# ASL2111.net
KiCad netlist of a schematic drawn in EAGLE
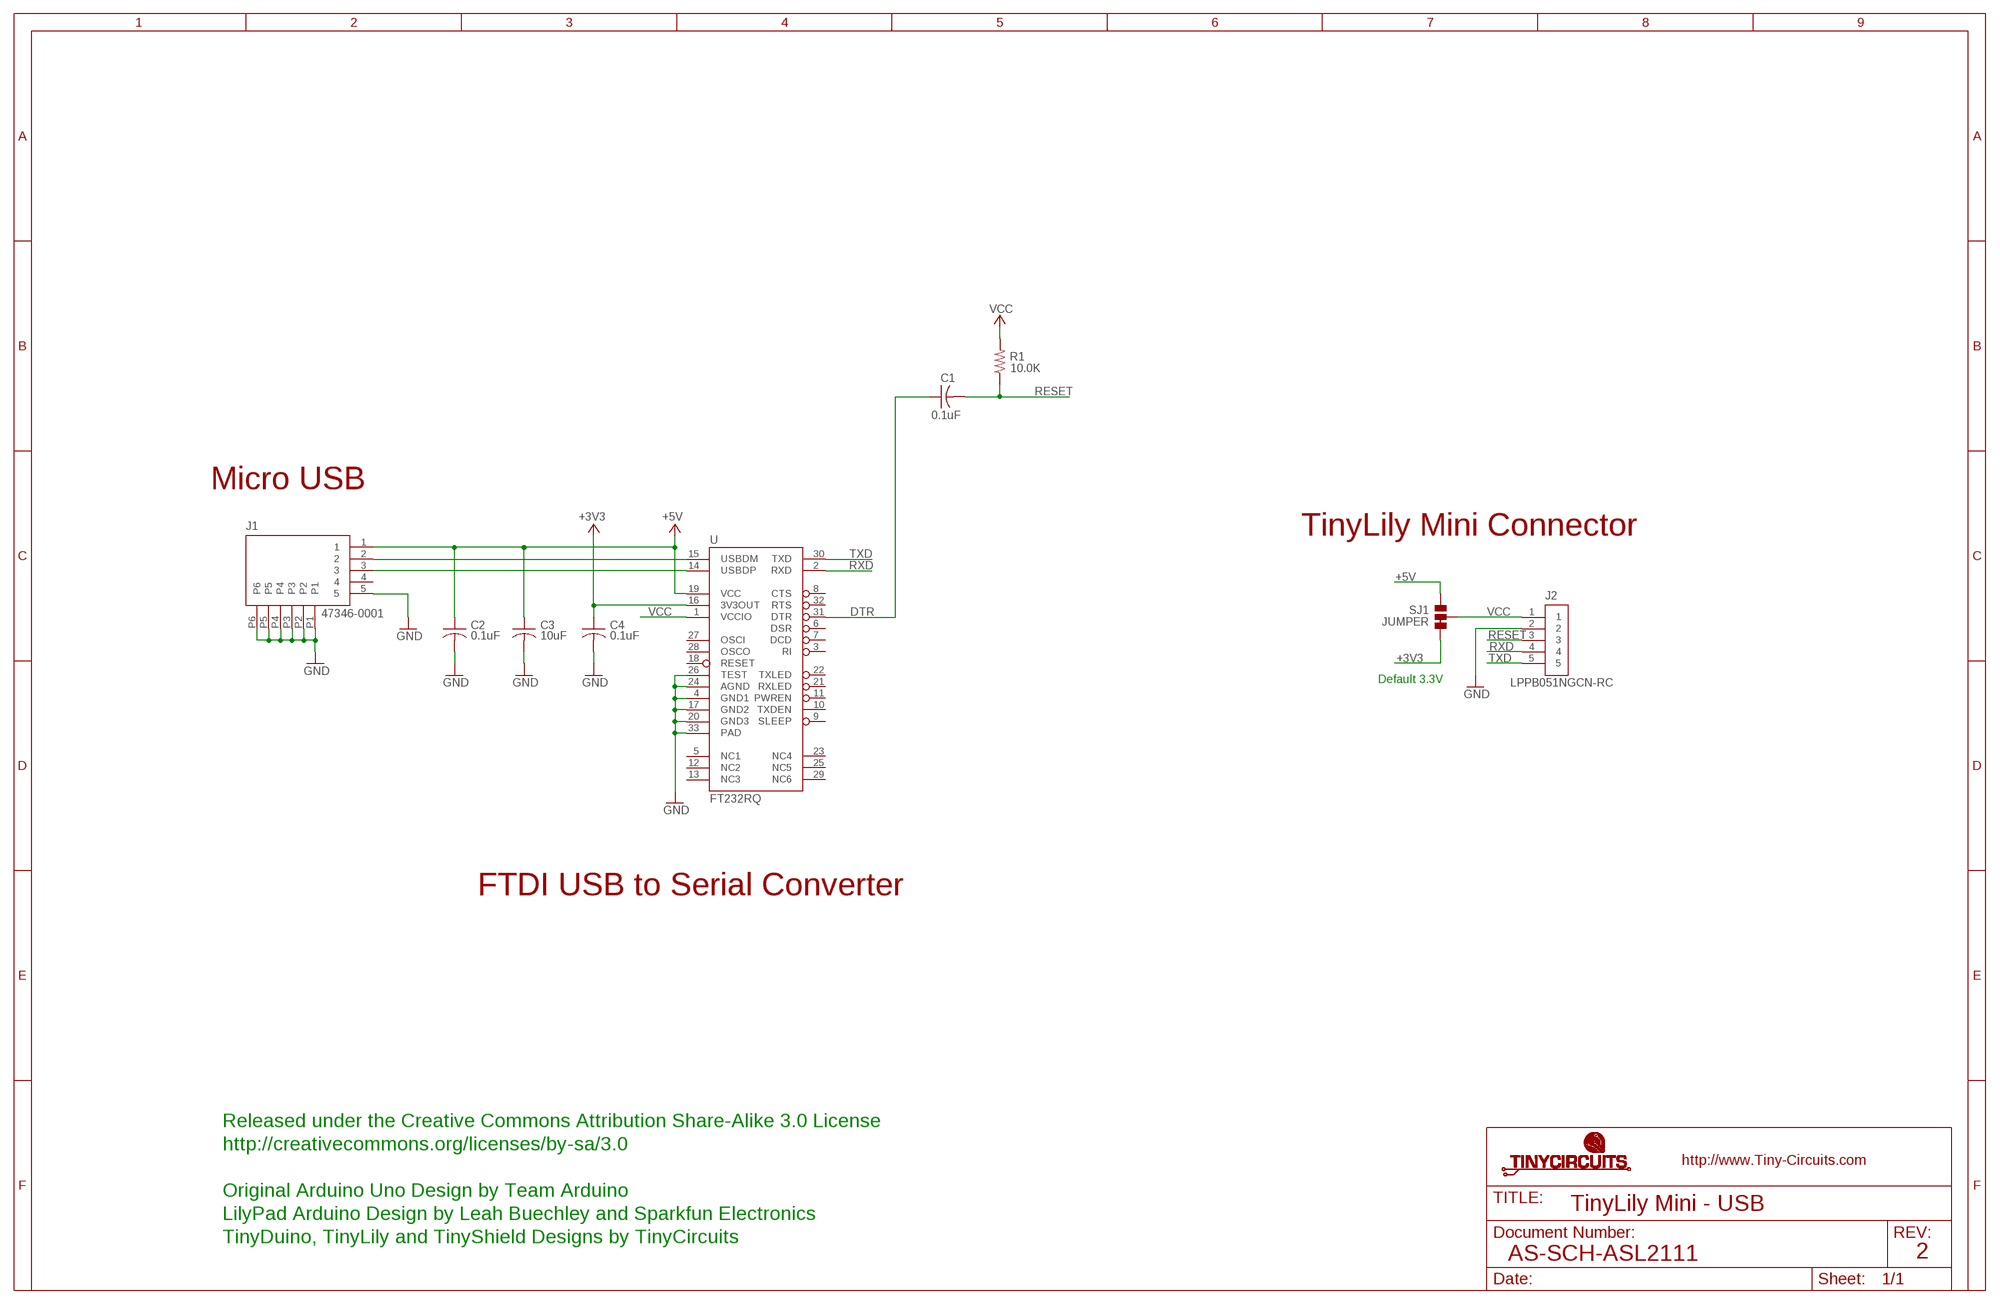
[diagram p0: schematic, sheet 1]

(export (version "E")
  (design (tool "Eeschema 10.0.6"))
  (components
    (comp (ref "C1")
      (value "0.1uF")
      (footprint "eagle-import:C0402")
      (fields (field (name "PARTNO") "AS-ITM-00008") (field (name "PARTNO_1") "AS-ITM-00008"))
      (libsource (lib "eagle-import") (part "AS-ITM-00008"))
    )
    (comp (ref "C2")
      (value "0.1uF")
      (footprint "eagle-import:C0402")
      (fields (field (name "PARTNO") "AS-ITM-00008"))
      (libsource (lib "eagle-import") (part "AS-ITM-00008"))
    )
    (comp (ref "C3")
      (value "10uF")
      (footprint "eagle-import:C0603")
      (fields (field (name "PARTNO") "AS-ITM-00002"))
      (libsource (lib "eagle-import") (part "AS-ITM-00002"))
    )
    (comp (ref "C4")
      (value "0.1uF")
      (footprint "eagle-import:C0402")
      (fields (field (name "PARTNO") "AS-ITM-00008") (field (name "PARTNO_1") "AS-ITM-00008"))
      (libsource (lib "eagle-import") (part "AS-ITM-00008"))
    )
    (comp (ref "J1")
      (value "47346-0001")
      (footprint "eagle-import:MICRO_USB")
      (fields (field (name "PARTNO") "AS-ITM-00021") (field (name "PARTNO_1") "AS-ITM-00021"))
      (libsource (lib "eagle-import") (part "AS-ITM-00021"))
    )
    (comp (ref "J2")
      (value "LPPB051NGCN-RC")
      (footprint "eagle-import:1X5_.05_RA_TH_RECPT")
      (fields (field (name "PARTNO") "AS-ITM-00037"))
      (libsource (lib "eagle-import") (part "AS-ITM-00037"))
    )
    (comp (ref "R1")
      (value "10.0K")
      (footprint "eagle-import:0402")
      (fields (field (name "PARTNO") "AS-ITM-00032"))
      (libsource (lib "eagle-import") (part "AS-ITM-00032"))
    )
    (comp (ref "SJ1")
      (value "JUMPER")
      (footprint "eagle-import:JUMPER_0402")
      (fields (field (name "PARTNO") "AS-ITM-00033"))
      (libsource (lib "eagle-import") (part "AS-ITM-00033"))
    )
    (comp (ref "U")
      (value "FT232RQ")
      (footprint "eagle-import:MLF32")
      (fields (field (name "PARTNO") "AS-ITM-00029"))
      (libsource (lib "eagle-import") (part "AS-ITM-00029"))
    )
  )
  (nets
    (net (code "1") (name "+3V3") (class "Default")
      (node (ref "C4") (pin "1") (pinfunction "1_1") (pintype "passive"))
      (node (ref "SJ1") (pin "2") (pinfunction "2_2") (pintype "passive"))
      (node (ref "U") (pin "16") (pinfunction "3V3OUT_16") (pintype "power_in"))
    )
    (net (code "2") (name "+5V") (class "Default")
      (node (ref "C2") (pin "1") (pinfunction "1_1") (pintype "passive"))
      (node (ref "C3") (pin "1") (pinfunction "1_1") (pintype "passive"))
      (node (ref "J1") (pin "1") (pinfunction "1_1") (pintype "bidirectional"))
      (node (ref "SJ1") (pin "3") (pinfunction "3_3") (pintype "passive"))
      (node (ref "U") (pin "19") (pinfunction "VCC_19") (pintype "power_in"))
    )
    (net (code "3") (name "/DTR") (class "Default")
      (node (ref "C1") (pin "1") (pinfunction "1_1") (pintype "passive"))
      (node (ref "U") (pin "31") (pinfunction "DTR_31") (pintype "bidirectional"))
    )
    (net (code "4") (name "/RESET") (class "Default")
      (node (ref "C1") (pin "2") (pinfunction "2_2") (pintype "passive"))
      (node (ref "J2") (pin "3") (pinfunction "3_3") (pintype "bidirectional"))
      (node (ref "R1") (pin "1") (pinfunction "1_1") (pintype "passive"))
    )
    (net (code "5") (name "/RXD") (class "Default")
      (node (ref "J2") (pin "4") (pinfunction "4_4") (pintype "bidirectional"))
      (node (ref "U") (pin "2") (pinfunction "RXD_2") (pintype "bidirectional"))
    )
    (net (code "6") (name "/TXD") (class "Default")
      (node (ref "J2") (pin "5") (pinfunction "5_5") (pintype "bidirectional"))
      (node (ref "U") (pin "30") (pinfunction "TXD_30") (pintype "bidirectional"))
    )
    (net (code "7") (name "GND") (class "Default")
      (node (ref "C2") (pin "2") (pinfunction "2_2") (pintype "passive"))
      (node (ref "C3") (pin "2") (pinfunction "2_2") (pintype "passive"))
      (node (ref "C4") (pin "2") (pinfunction "2_2") (pintype "passive"))
      (node (ref "J1") (pin "5") (pinfunction "5_5") (pintype "bidirectional"))
      (node (ref "J1") (pin "P1") (pinfunction "P1_P1") (pintype "bidirectional"))
      (node (ref "J1") (pin "P2") (pinfunction "P2_P2") (pintype "bidirectional"))
      (node (ref "J1") (pin "P3") (pinfunction "P3_P3") (pintype "bidirectional"))
      (node (ref "J1") (pin "P4") (pinfunction "P4_P4") (pintype "bidirectional"))
      (node (ref "J1") (pin "P5") (pinfunction "P5_P5") (pintype "bidirectional"))
      (node (ref "J1") (pin "P6") (pinfunction "P6_P6") (pintype "bidirectional"))
      (node (ref "J2") (pin "2") (pinfunction "2_2") (pintype "bidirectional"))
      (node (ref "U") (pin "17") (pinfunction "GND2_17") (pintype "power_in"))
      (node (ref "U") (pin "20") (pinfunction "GND3_20") (pintype "power_in"))
      (node (ref "U") (pin "24") (pinfunction "AGND_24") (pintype "bidirectional"))
      (node (ref "U") (pin "26") (pinfunction "TEST_26") (pintype "bidirectional"))
      (node (ref "U") (pin "33") (pinfunction "PAD_33") (pintype "power_in"))
      (node (ref "U") (pin "4") (pinfunction "GND1_4") (pintype "power_in"))
    )
    (net (code "8") (name "Net-(U-USBDM)") (class "Default")
      (node (ref "J1") (pin "2") (pinfunction "2_2") (pintype "bidirectional"))
      (node (ref "U") (pin "15") (pinfunction "USBDM_15") (pintype "bidirectional"))
    )
    (net (code "9") (name "Net-(U-USBDP)") (class "Default")
      (node (ref "J1") (pin "3") (pinfunction "3_3") (pintype "bidirectional"))
      (node (ref "U") (pin "14") (pinfunction "USBDP_14") (pintype "bidirectional"))
    )
    (net (code "10") (name "VCC") (class "Default")
      (node (ref "J2") (pin "1") (pinfunction "1_1") (pintype "bidirectional"))
      (node (ref "R1") (pin "2") (pinfunction "2_2") (pintype "passive"))
      (node (ref "SJ1") (pin "1") (pinfunction "1_1") (pintype "passive"))
      (node (ref "U") (pin "1") (pinfunction "VCCIO_1") (pintype "power_in"))
    )
    (net (code "11") (name "unconnected-(J1-Pad4)") (class "Default")
      (node (ref "J1") (pin "4") (pinfunction "4_4") (pintype "bidirectional"))
    )
    (net (code "12") (name "unconnected-(U-CTS-Pad8)") (class "Default")
      (node (ref "U") (pin "8") (pinfunction "CTS_8") (pintype "bidirectional"))
    )
    (net (code "13") (name "unconnected-(U-DCD-Pad7)") (class "Default")
      (node (ref "U") (pin "7") (pinfunction "DCD_7") (pintype "bidirectional"))
    )
    (net (code "14") (name "unconnected-(U-DSR-Pad6)") (class "Default")
      (node (ref "U") (pin "6") (pinfunction "DSR_6") (pintype "bidirectional"))
    )
    (net (code "15") (name "unconnected-(U-NC1-Pad5)") (class "Default")
      (node (ref "U") (pin "5") (pinfunction "NC1_5") (pintype "bidirectional"))
    )
    (net (code "16") (name "unconnected-(U-NC2-Pad12)") (class "Default")
      (node (ref "U") (pin "12") (pinfunction "NC2_12") (pintype "bidirectional"))
    )
    (net (code "17") (name "unconnected-(U-NC3-Pad13)") (class "Default")
      (node (ref "U") (pin "13") (pinfunction "NC3_13") (pintype "bidirectional"))
    )
    (net (code "18") (name "unconnected-(U-NC4-Pad23)") (class "Default")
      (node (ref "U") (pin "23") (pinfunction "NC4_23") (pintype "bidirectional"))
    )
    (net (code "19") (name "unconnected-(U-NC5-Pad25)") (class "Default")
      (node (ref "U") (pin "25") (pinfunction "NC5_25") (pintype "bidirectional"))
    )
    (net (code "20") (name "unconnected-(U-NC6-Pad29)") (class "Default")
      (node (ref "U") (pin "29") (pinfunction "NC6_29") (pintype "bidirectional"))
    )
    (net (code "21") (name "unconnected-(U-OSCI-Pad27)") (class "Default")
      (node (ref "U") (pin "27") (pinfunction "OSCI_27") (pintype "bidirectional"))
    )
    (net (code "22") (name "unconnected-(U-OSCO-Pad28)") (class "Default")
      (node (ref "U") (pin "28") (pinfunction "OSCO_28") (pintype "bidirectional"))
    )
    (net (code "23") (name "unconnected-(U-PWREN-Pad11)") (class "Default")
      (node (ref "U") (pin "11") (pinfunction "PWREN_11") (pintype "bidirectional"))
    )
    (net (code "24") (name "unconnected-(U-RESET-Pad18)") (class "Default")
      (node (ref "U") (pin "18") (pinfunction "RESET_18") (pintype "bidirectional"))
    )
    (net (code "25") (name "unconnected-(U-RI-Pad3)") (class "Default")
      (node (ref "U") (pin "3") (pinfunction "RI_3") (pintype "bidirectional"))
    )
    (net (code "26") (name "unconnected-(U-RTS-Pad32)") (class "Default")
      (node (ref "U") (pin "32") (pinfunction "RTS_32") (pintype "bidirectional"))
    )
    (net (code "27") (name "unconnected-(U-RXLED-Pad21)") (class "Default")
      (node (ref "U") (pin "21") (pinfunction "RXLED_21") (pintype "bidirectional"))
    )
    (net (code "28") (name "unconnected-(U-SLEEP-Pad9)") (class "Default")
      (node (ref "U") (pin "9") (pinfunction "SLEEP_9") (pintype "bidirectional"))
    )
    (net (code "29") (name "unconnected-(U-TXDEN-Pad10)") (class "Default")
      (node (ref "U") (pin "10") (pinfunction "TXDEN_10") (pintype "bidirectional"))
    )
    (net (code "30") (name "unconnected-(U-TXLED-Pad22)") (class "Default")
      (node (ref "U") (pin "22") (pinfunction "TXLED_22") (pintype "bidirectional"))
    )
  )
)
